# MazeSolverPCB_v_0_3.net
KiCad netlist of a schematic drawn in EAGLE
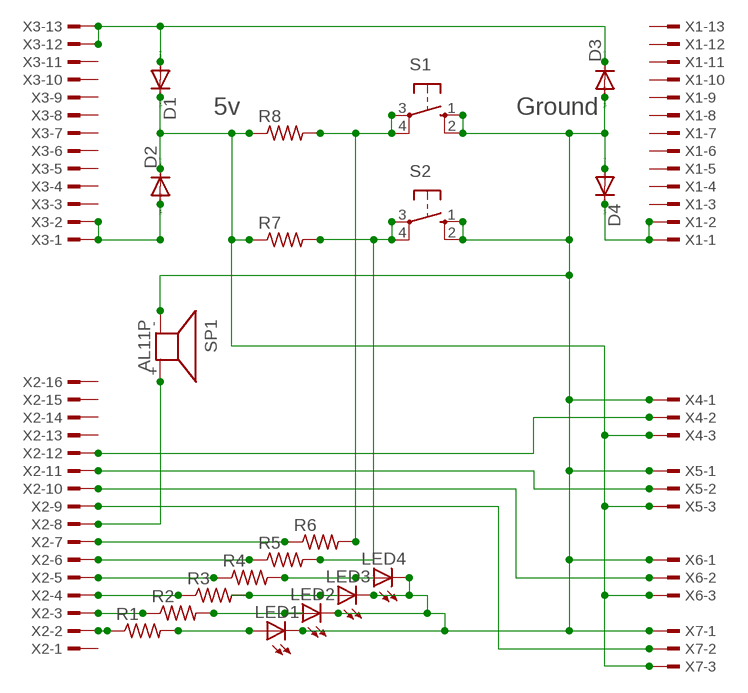
[diagram p0: schematic, sheet 1]

(export (version "E")
  (design (tool "Eeschema 10.0.6"))
  (components
    (comp (ref "D1")
      (value "1N4004")
      (footprint "eagle-import:DO41-10")
      (libsource (lib "eagle-import") (part "1N4004"))
    )
    (comp (ref "D2")
      (value "1N4004")
      (footprint "eagle-import:DO41-10")
      (libsource (lib "eagle-import") (part "1N4004"))
    )
    (comp (ref "D3")
      (value "1N4004")
      (footprint "eagle-import:DO41-10")
      (libsource (lib "eagle-import") (part "1N4004"))
    )
    (comp (ref "D4")
      (value "1N4004")
      (footprint "eagle-import:DO41-10")
      (libsource (lib "eagle-import") (part "1N4004"))
    )
    (comp (ref "LED1")
      (value "TLLG4400")
      (footprint "eagle-import:LED3MM")
      (fields (field (name "MF") "VISHAY SEMICONDUCTOR"))
      (libsource (lib "eagle-import") (part "TLLG4400"))
    )
    (comp (ref "LED2")
      (value "TLLG4400")
      (footprint "eagle-import:LED3MM")
      (fields (field (name "MF") "VISHAY SEMICONDUCTOR"))
      (libsource (lib "eagle-import") (part "TLLG4400"))
    )
    (comp (ref "LED3")
      (value "TLLG4400")
      (footprint "eagle-import:LED3MM")
      (fields (field (name "MF") "VISHAY SEMICONDUCTOR"))
      (libsource (lib "eagle-import") (part "TLLG4400"))
    )
    (comp (ref "LED4")
      (value "TLLG4400")
      (footprint "eagle-import:LED3MM")
      (fields (field (name "MF") "VISHAY SEMICONDUCTOR"))
      (libsource (lib "eagle-import") (part "TLLG4400"))
    )
    (comp (ref "R1")
      (value "R-US_0207/7")
      (footprint "eagle-import:0207_7")
      (libsource (lib "eagle-import") (part "R-US_0207/7"))
    )
    (comp (ref "R2")
      (value "R-US_0207/7")
      (footprint "eagle-import:0207_7")
      (libsource (lib "eagle-import") (part "R-US_0207/7"))
    )
    (comp (ref "R3")
      (value "R-US_0207/7")
      (footprint "eagle-import:0207_7")
      (libsource (lib "eagle-import") (part "R-US_0207/7"))
    )
    (comp (ref "R4")
      (value "R-US_0207/7")
      (footprint "eagle-import:0207_7")
      (libsource (lib "eagle-import") (part "R-US_0207/7"))
    )
    (comp (ref "R5")
      (value "R-US_0207/7")
      (footprint "eagle-import:0207_7")
      (libsource (lib "eagle-import") (part "R-US_0207/7"))
    )
    (comp (ref "R6")
      (value "R-US_0207/7")
      (footprint "eagle-import:0207_7")
      (libsource (lib "eagle-import") (part "R-US_0207/7"))
    )
    (comp (ref "R7")
      (value "R-US_0207/7")
      (footprint "eagle-import:0207_7")
      (libsource (lib "eagle-import") (part "R-US_0207/7"))
    )
    (comp (ref "R8")
      (value "R-US_0207/7")
      (footprint "eagle-import:0207_7")
      (libsource (lib "eagle-import") (part "R-US_0207/7"))
    )
    (comp (ref "S1")
      (value "10-XX")
      (footprint "eagle-import:B3F-10XX")
      (fields (field (name "MPN") "B3F-1000"))
      (libsource (lib "eagle-import") (part "10-XX"))
    )
    (comp (ref "S2")
      (value "10-XX")
      (footprint "eagle-import:B3F-10XX")
      (fields (field (name "MPN") "B3F-1000"))
      (libsource (lib "eagle-import") (part "10-XX"))
    )
    (comp (ref "SP1")
      (value "AL11P")
      (footprint "eagle-import:AL11P")
      (libsource (lib "eagle-import") (part "AL11P"))
    )
    (comp (ref "X1")
      (value "TSW-113-02-S-S")
      (footprint "eagle-import:TSW-113-02-S-S")
      (libsource (lib "eagle-import") (part "TSW-113-02-S-S"))
    )
    (comp (ref "X2")
      (value "TSW-116-02-S-S")
      (footprint "eagle-import:TSW-116-02-S-S")
      (libsource (lib "eagle-import") (part "TSW-116-02-S-S"))
    )
    (comp (ref "X3")
      (value "TSW-113-02-S-S")
      (footprint "eagle-import:TSW-113-02-S-S")
      (libsource (lib "eagle-import") (part "TSW-113-02-S-S"))
    )
    (comp (ref "X4")
      (value "TSW-103-02-S-S")
      (footprint "eagle-import:TSW-103-02-S-S")
      (libsource (lib "eagle-import") (part "TSW-103-02-S-S"))
    )
    (comp (ref "X5")
      (value "TSW-103-02-S-S")
      (footprint "eagle-import:TSW-103-02-S-S")
      (libsource (lib "eagle-import") (part "TSW-103-02-S-S"))
    )
    (comp (ref "X6")
      (value "TSW-103-02-S-S")
      (footprint "eagle-import:TSW-103-02-S-S")
      (libsource (lib "eagle-import") (part "TSW-103-02-S-S"))
    )
    (comp (ref "X7")
      (value "TSW-103-02-S-S")
      (footprint "eagle-import:TSW-103-02-S-S")
      (libsource (lib "eagle-import") (part "TSW-103-02-S-S"))
    )
  )
  (nets
    (net (code "1") (name "Net-(LED1-C)") (class "Default")
      (node (ref "D3") (pin "A") (pinfunction "A_A") (pintype "passive"))
      (node (ref "D4") (pin "A") (pinfunction "A_A") (pintype "passive"))
      (node (ref "LED1") (pin "K") (pinfunction "C_K") (pintype "passive"))
      (node (ref "LED2") (pin "K") (pinfunction "C_K") (pintype "passive"))
      (node (ref "LED3") (pin "K") (pinfunction "C_K") (pintype "passive"))
      (node (ref "LED4") (pin "K") (pinfunction "C_K") (pintype "passive"))
      (node (ref "S1") (pin "1") (pinfunction "S_1") (pintype "passive"))
      (node (ref "S1") (pin "2") (pinfunction "S1_2") (pintype "passive"))
      (node (ref "S2") (pin "1") (pinfunction "S_1") (pintype "passive"))
      (node (ref "S2") (pin "2") (pinfunction "S1_2") (pintype "passive"))
      (node (ref "SP1") (pin "-") (pinfunction "1_-") (pintype "passive"))
      (node (ref "X4") (pin "1") (pinfunction "1_1") (pintype "passive"))
      (node (ref "X5") (pin "1") (pinfunction "1_1") (pintype "passive"))
      (node (ref "X6") (pin "1") (pinfunction "1_1") (pintype "passive"))
      (node (ref "X7") (pin "1") (pinfunction "1_1") (pintype "passive"))
    )
    (net (code "2") (name "Net-(LED1-PadA)") (class "Default")
      (node (ref "LED1") (pin "A") (pinfunction "A_A") (pintype "passive"))
      (node (ref "R1") (pin "2") (pinfunction "2_2") (pintype "passive"))
    )
    (net (code "3") (name "Net-(LED2-PadA)") (class "Default")
      (node (ref "LED2") (pin "A") (pinfunction "A_A") (pintype "passive"))
      (node (ref "R2") (pin "2") (pinfunction "2_2") (pintype "passive"))
    )
    (net (code "4") (name "Net-(LED3-PadA)") (class "Default")
      (node (ref "LED3") (pin "A") (pinfunction "A_A") (pintype "passive"))
      (node (ref "R3") (pin "2") (pinfunction "2_2") (pintype "passive"))
    )
    (net (code "5") (name "Net-(LED4-PadA)") (class "Default")
      (node (ref "LED4") (pin "A") (pinfunction "A_A") (pintype "passive"))
      (node (ref "R4") (pin "2") (pinfunction "2_2") (pintype "passive"))
    )
    (net (code "6") (name "Net-(S1-P)") (class "Default")
      (node (ref "R6") (pin "2") (pinfunction "2_2") (pintype "passive"))
      (node (ref "R8") (pin "2") (pinfunction "2_2") (pintype "passive"))
      (node (ref "S1") (pin "3") (pinfunction "P_3") (pintype "passive"))
      (node (ref "S1") (pin "4") (pinfunction "P1_4") (pintype "passive"))
    )
    (net (code "7") (name "Net-(S2-P)") (class "Default")
      (node (ref "R5") (pin "2") (pinfunction "2_2") (pintype "passive"))
      (node (ref "R7") (pin "2") (pinfunction "2_2") (pintype "passive"))
      (node (ref "S2") (pin "3") (pinfunction "P_3") (pintype "passive"))
      (node (ref "S2") (pin "4") (pinfunction "P1_4") (pintype "passive"))
    )
    (net (code "8") (name "Net-(SP1-2)") (class "Default")
      (node (ref "SP1") (pin "+") (pinfunction "2_+") (pintype "passive"))
      (node (ref "X2") (pin "8") (pinfunction "1_8") (pintype "passive"))
    )
    (net (code "9") (name "Net-(X1F-1)") (class "Default")
      (node (ref "D4") (pin "C") (pinfunction "C_C") (pintype "passive"))
      (node (ref "X1") (pin "1") (pinfunction "1_1") (pintype "passive"))
      (node (ref "X1") (pin "2") (pinfunction "1_2") (pintype "passive"))
    )
    (net (code "10") (name "Net-(X2B-1)") (class "Default")
      (node (ref "X2") (pin "10") (pinfunction "1_10") (pintype "passive"))
      (node (ref "X6") (pin "2") (pinfunction "1_2") (pintype "passive"))
    )
    (net (code "11") (name "Net-(X2C-1)") (class "Default")
      (node (ref "X2") (pin "11") (pinfunction "1_11") (pintype "passive"))
      (node (ref "X5") (pin "2") (pinfunction "1_2") (pintype "passive"))
    )
    (net (code "12") (name "Net-(X2D-1)") (class "Default")
      (node (ref "X2") (pin "12") (pinfunction "1_12") (pintype "passive"))
      (node (ref "X4") (pin "2") (pinfunction "1_2") (pintype "passive"))
    )
    (net (code "13") (name "Net-(X2I-1)") (class "Default")
      (node (ref "R1") (pin "1") (pinfunction "1_1") (pintype "passive"))
      (node (ref "X2") (pin "2") (pinfunction "1_2") (pintype "passive"))
    )
    (net (code "14") (name "Net-(X2J-1)") (class "Default")
      (node (ref "R2") (pin "1") (pinfunction "1_1") (pintype "passive"))
      (node (ref "X2") (pin "3") (pinfunction "1_3") (pintype "passive"))
    )
    (net (code "15") (name "Net-(X2K-1)") (class "Default")
      (node (ref "R3") (pin "1") (pinfunction "1_1") (pintype "passive"))
      (node (ref "X2") (pin "4") (pinfunction "1_4") (pintype "passive"))
    )
    (net (code "16") (name "Net-(X2L-1)") (class "Default")
      (node (ref "R4") (pin "1") (pinfunction "1_1") (pintype "passive"))
      (node (ref "X2") (pin "5") (pinfunction "1_5") (pintype "passive"))
    )
    (net (code "17") (name "Net-(X2M-1)") (class "Default")
      (node (ref "R5") (pin "1") (pinfunction "1_1") (pintype "passive"))
      (node (ref "X2") (pin "6") (pinfunction "1_6") (pintype "passive"))
    )
    (net (code "18") (name "Net-(X2N-1)") (class "Default")
      (node (ref "R6") (pin "1") (pinfunction "1_1") (pintype "passive"))
      (node (ref "X2") (pin "7") (pinfunction "1_7") (pintype "passive"))
    )
    (net (code "19") (name "Net-(X2P-1)") (class "Default")
      (node (ref "X2") (pin "9") (pinfunction "1_9") (pintype "passive"))
      (node (ref "X7") (pin "2") (pinfunction "1_2") (pintype "passive"))
    )
    (net (code "20") (name "Net-(X3D-1)") (class "Default")
      (node (ref "D1") (pin "A") (pinfunction "A_A") (pintype "passive"))
      (node (ref "D3") (pin "C") (pinfunction "C_C") (pintype "passive"))
      (node (ref "X3") (pin "12") (pinfunction "1_12") (pintype "passive"))
      (node (ref "X3") (pin "13") (pinfunction "1_13") (pintype "passive"))
    )
    (net (code "21") (name "Net-(X3F-1)") (class "Default")
      (node (ref "D2") (pin "A") (pinfunction "A_A") (pintype "passive"))
      (node (ref "X3") (pin "1") (pinfunction "1_1") (pintype "passive"))
      (node (ref "X3") (pin "2") (pinfunction "1_2") (pintype "passive"))
    )
    (net (code "22") (name "Net-(X4C-1)") (class "Default")
      (node (ref "D1") (pin "C") (pinfunction "C_C") (pintype "passive"))
      (node (ref "D2") (pin "C") (pinfunction "C_C") (pintype "passive"))
      (node (ref "R7") (pin "1") (pinfunction "1_1") (pintype "passive"))
      (node (ref "R8") (pin "1") (pinfunction "1_1") (pintype "passive"))
      (node (ref "X4") (pin "3") (pinfunction "1_3") (pintype "passive"))
      (node (ref "X5") (pin "3") (pinfunction "1_3") (pintype "passive"))
      (node (ref "X6") (pin "3") (pinfunction "1_3") (pintype "passive"))
      (node (ref "X7") (pin "3") (pinfunction "1_3") (pintype "passive"))
    )
    (net (code "23") (name "unconnected-(X1B-1-Pad10)") (class "Default")
      (node (ref "X1") (pin "10") (pinfunction "1_10") (pintype "passive"))
    )
    (net (code "24") (name "unconnected-(X1C-1-Pad11)") (class "Default")
      (node (ref "X1") (pin "11") (pinfunction "1_11") (pintype "passive"))
    )
    (net (code "25") (name "unconnected-(X1D-1-Pad12)") (class "Default")
      (node (ref "X1") (pin "12") (pinfunction "1_12") (pintype "passive"))
    )
    (net (code "26") (name "unconnected-(X1E-1-Pad13)") (class "Default")
      (node (ref "X1") (pin "13") (pinfunction "1_13") (pintype "passive"))
    )
    (net (code "27") (name "unconnected-(X1G-1-Pad3)") (class "Default")
      (node (ref "X1") (pin "3") (pinfunction "1_3") (pintype "passive"))
    )
    (net (code "28") (name "unconnected-(X1H-1-Pad4)") (class "Default")
      (node (ref "X1") (pin "4") (pinfunction "1_4") (pintype "passive"))
    )
    (net (code "29") (name "unconnected-(X1I-1-Pad5)") (class "Default")
      (node (ref "X1") (pin "5") (pinfunction "1_5") (pintype "passive"))
    )
    (net (code "30") (name "unconnected-(X1J-1-Pad6)") (class "Default")
      (node (ref "X1") (pin "6") (pinfunction "1_6") (pintype "passive"))
    )
    (net (code "31") (name "unconnected-(X1K-1-Pad7)") (class "Default")
      (node (ref "X1") (pin "7") (pinfunction "1_7") (pintype "passive"))
    )
    (net (code "32") (name "unconnected-(X1L-1-Pad8)") (class "Default")
      (node (ref "X1") (pin "8") (pinfunction "1_8") (pintype "passive"))
    )
    (net (code "33") (name "unconnected-(X1M-1-Pad9)") (class "Default")
      (node (ref "X1") (pin "9") (pinfunction "1_9") (pintype "passive"))
    )
    (net (code "34") (name "unconnected-(X2-Pad1)") (class "Default")
      (node (ref "X2") (pin "1") (pinfunction "1_1") (pintype "passive"))
    )
    (net (code "35") (name "unconnected-(X2E-1-Pad13)") (class "Default")
      (node (ref "X2") (pin "13") (pinfunction "1_13") (pintype "passive"))
    )
    (net (code "36") (name "unconnected-(X2F-1-Pad14)") (class "Default")
      (node (ref "X2") (pin "14") (pinfunction "1_14") (pintype "passive"))
    )
    (net (code "37") (name "unconnected-(X2G-1-Pad15)") (class "Default")
      (node (ref "X2") (pin "15") (pinfunction "1_15") (pintype "passive"))
    )
    (net (code "38") (name "unconnected-(X2H-1-Pad16)") (class "Default")
      (node (ref "X2") (pin "16") (pinfunction "1_16") (pintype "passive"))
    )
    (net (code "39") (name "unconnected-(X3B-1-Pad10)") (class "Default")
      (node (ref "X3") (pin "10") (pinfunction "1_10") (pintype "passive"))
    )
    (net (code "40") (name "unconnected-(X3C-1-Pad11)") (class "Default")
      (node (ref "X3") (pin "11") (pinfunction "1_11") (pintype "passive"))
    )
    (net (code "41") (name "unconnected-(X3G-1-Pad3)") (class "Default")
      (node (ref "X3") (pin "3") (pinfunction "1_3") (pintype "passive"))
    )
    (net (code "42") (name "unconnected-(X3H-1-Pad4)") (class "Default")
      (node (ref "X3") (pin "4") (pinfunction "1_4") (pintype "passive"))
    )
    (net (code "43") (name "unconnected-(X3I-1-Pad5)") (class "Default")
      (node (ref "X3") (pin "5") (pinfunction "1_5") (pintype "passive"))
    )
    (net (code "44") (name "unconnected-(X3J-1-Pad6)") (class "Default")
      (node (ref "X3") (pin "6") (pinfunction "1_6") (pintype "passive"))
    )
    (net (code "45") (name "unconnected-(X3K-1-Pad7)") (class "Default")
      (node (ref "X3") (pin "7") (pinfunction "1_7") (pintype "passive"))
    )
    (net (code "46") (name "unconnected-(X3L-1-Pad8)") (class "Default")
      (node (ref "X3") (pin "8") (pinfunction "1_8") (pintype "passive"))
    )
    (net (code "47") (name "unconnected-(X3M-1-Pad9)") (class "Default")
      (node (ref "X3") (pin "9") (pinfunction "1_9") (pintype "passive"))
    )
  )
)
